# Transistor_ckt.net
KiCad netlist of a schematic drawn in EAGLE
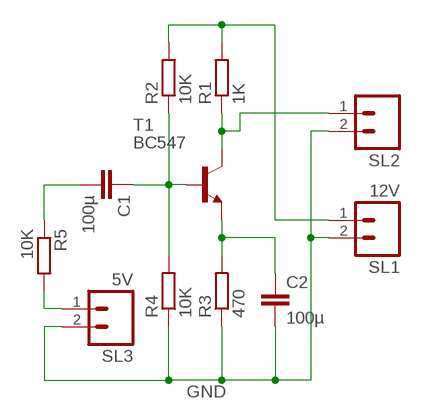
[diagram p0: schematic, sheet 1]

(export (version "E")
  (design (tool "Eeschema 10.0.6"))
  (components
    (comp (ref "C1")
      (value "100µ")
      (footprint "eagle-import:C025-025X050")
      (libsource (lib "eagle-import") (part "C-EU025-025X050"))
    )
    (comp (ref "C2")
      (value "100µ")
      (footprint "eagle-import:C025-025X050")
      (libsource (lib "eagle-import") (part "C-EU025-025X050"))
    )
    (comp (ref "R1")
      (value "1K")
      (footprint "eagle-import:0204_7")
      (libsource (lib "eagle-import") (part "R-EU_0204/7"))
    )
    (comp (ref "R2")
      (value "10K")
      (footprint "eagle-import:0204_7")
      (libsource (lib "eagle-import") (part "R-EU_0204/7"))
    )
    (comp (ref "R3")
      (value "470")
      (footprint "eagle-import:0204_7")
      (libsource (lib "eagle-import") (part "R-EU_0204/7"))
    )
    (comp (ref "R4")
      (value "10K")
      (footprint "eagle-import:0204_7")
      (libsource (lib "eagle-import") (part "R-EU_0204/7"))
    )
    (comp (ref "R5")
      (value "10K")
      (footprint "eagle-import:0204_7")
      (libsource (lib "eagle-import") (part "R-EU_0204/7"))
    )
    (comp (ref "SL1")
      (value "12V")
      (footprint "eagle-import:02P")
      (libsource (lib "eagle-import") (part "M02"))
    )
    (comp (ref "SL2")
      (value "M02")
      (footprint "eagle-import:02P")
      (libsource (lib "eagle-import") (part "M02"))
    )
    (comp (ref "SL3")
      (value "5V")
      (footprint "eagle-import:02P")
      (libsource (lib "eagle-import") (part "M02"))
    )
    (comp (ref "T1")
      (value "BC547")
      (footprint "eagle-import:TO92")
      (libsource (lib "eagle-import") (part "BC547"))
    )
  )
  (nets
    (net (code "1") (name "/GND") (class "Default")
      (node (ref "C2") (pin "2") (pinfunction "2_2") (pintype "passive"))
      (node (ref "R3") (pin "1") (pinfunction "1_1") (pintype "passive"))
      (node (ref "R4") (pin "1") (pinfunction "1_1") (pintype "passive"))
      (node (ref "SL1") (pin "2") (pinfunction "2_2") (pintype "passive"))
      (node (ref "SL2") (pin "2") (pinfunction "2_2") (pintype "passive"))
      (node (ref "SL3") (pin "2") (pinfunction "2_2") (pintype "passive"))
    )
    (net (code "2") (name "Net-(C1-Pad2)") (class "Default")
      (node (ref "C1") (pin "2") (pinfunction "2_2") (pintype "passive"))
      (node (ref "R5") (pin "1") (pinfunction "1_1") (pintype "passive"))
    )
    (net (code "3") (name "Net-(R1-Pad2)") (class "Default")
      (node (ref "R1") (pin "2") (pinfunction "2_2") (pintype "passive"))
      (node (ref "R2") (pin "2") (pinfunction "2_2") (pintype "passive"))
      (node (ref "SL1") (pin "1") (pinfunction "1_1") (pintype "passive"))
    )
    (net (code "4") (name "Net-(R5-Pad2)") (class "Default")
      (node (ref "R5") (pin "2") (pinfunction "2_2") (pintype "passive"))
      (node (ref "SL3") (pin "1") (pinfunction "1_1") (pintype "passive"))
    )
    (net (code "5") (name "Net-(T1-B)") (class "Default")
      (node (ref "C1") (pin "1") (pinfunction "1_1") (pintype "passive"))
      (node (ref "R2") (pin "1") (pinfunction "1_1") (pintype "passive"))
      (node (ref "R4") (pin "2") (pinfunction "2_2") (pintype "passive"))
      (node (ref "T1") (pin "2") (pinfunction "B_2") (pintype "passive"))
    )
    (net (code "6") (name "Net-(T1-C)") (class "Default")
      (node (ref "R1") (pin "1") (pinfunction "1_1") (pintype "passive"))
      (node (ref "SL2") (pin "1") (pinfunction "1_1") (pintype "passive"))
      (node (ref "T1") (pin "3") (pinfunction "C_3") (pintype "passive"))
    )
    (net (code "7") (name "Net-(T1-E)") (class "Default")
      (node (ref "C2") (pin "1") (pinfunction "1_1") (pintype "passive"))
      (node (ref "R3") (pin "2") (pinfunction "2_2") (pintype "passive"))
      (node (ref "T1") (pin "1") (pinfunction "E_1") (pintype "passive"))
    )
  )
)
